# mainAD2S1200.net
KiCad netlist of a schematic drawn in EAGLE
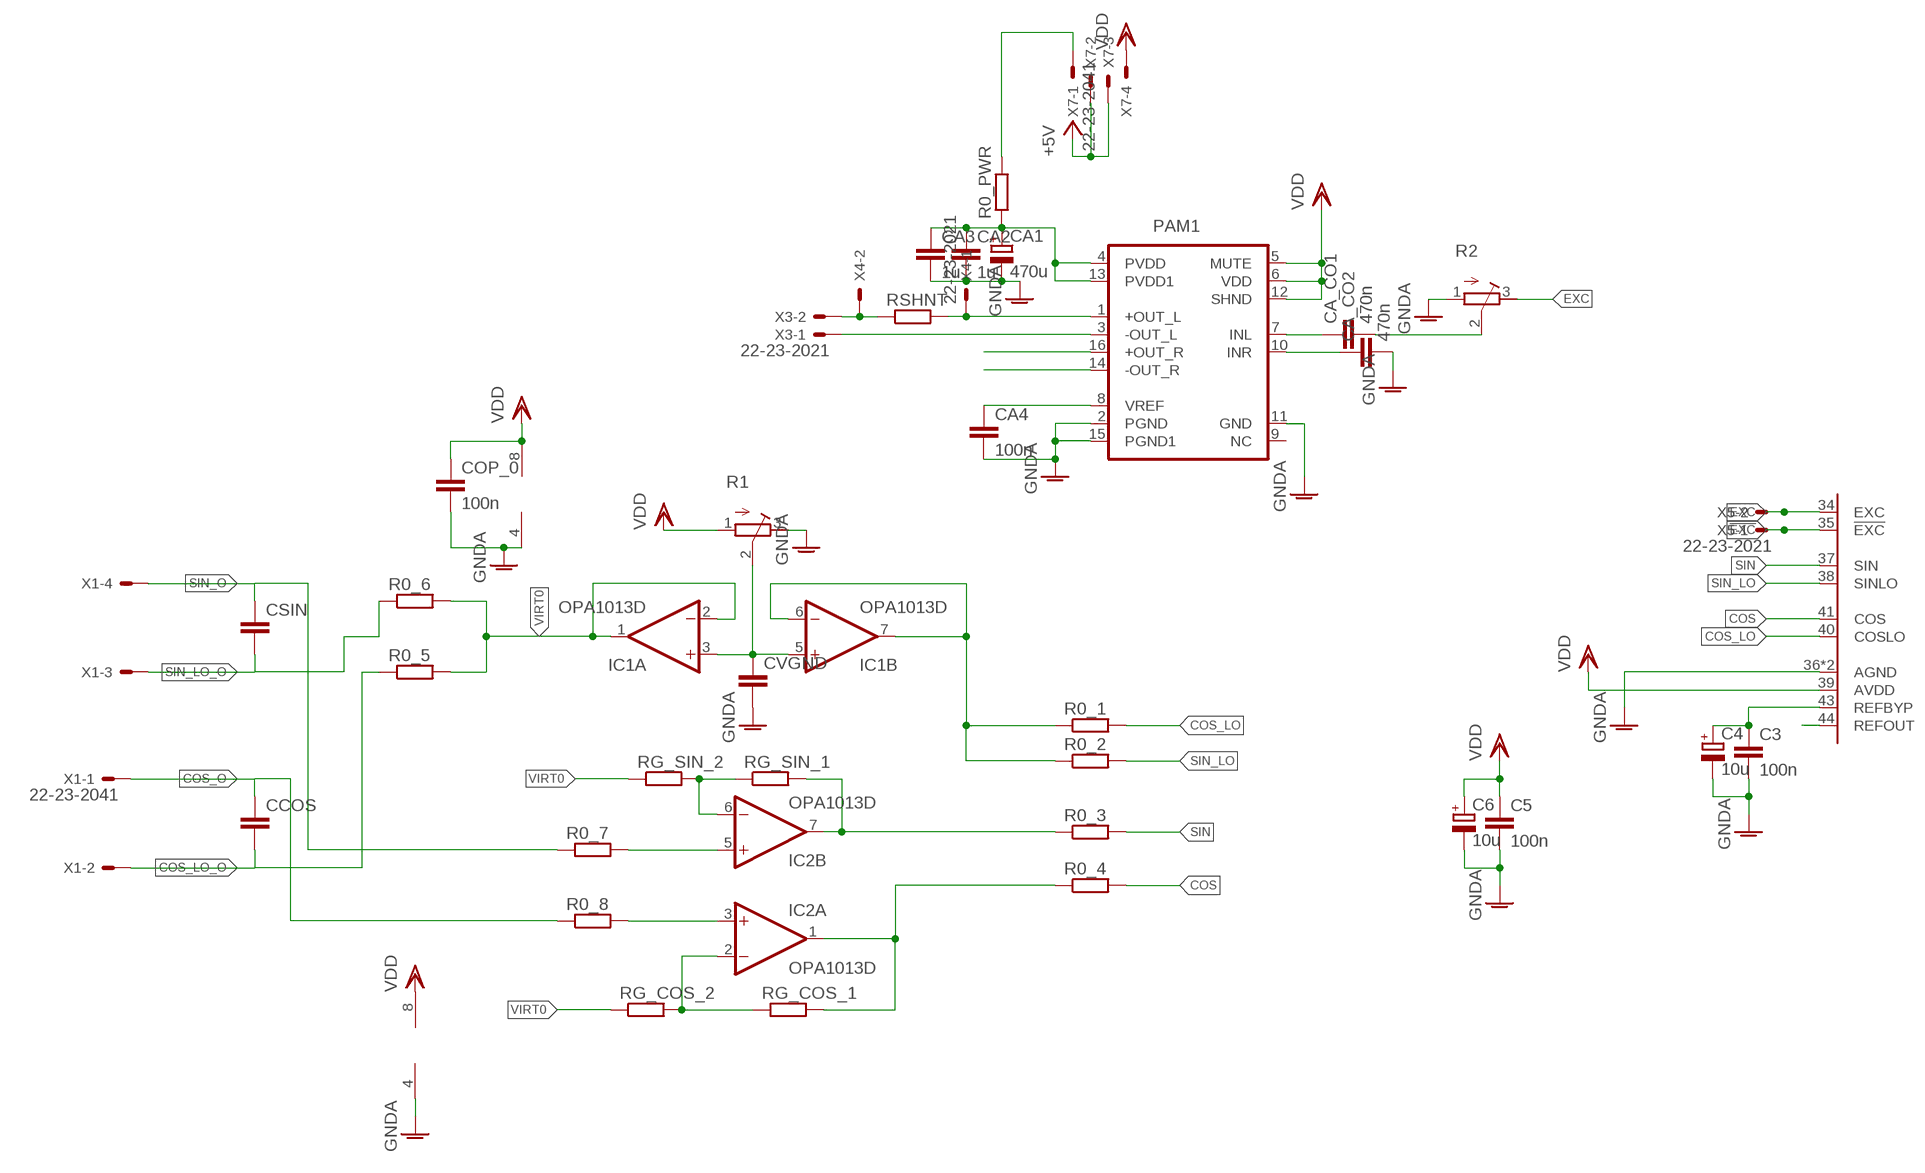
[diagram p0: schematic, sheet 1, part 1 of 2]
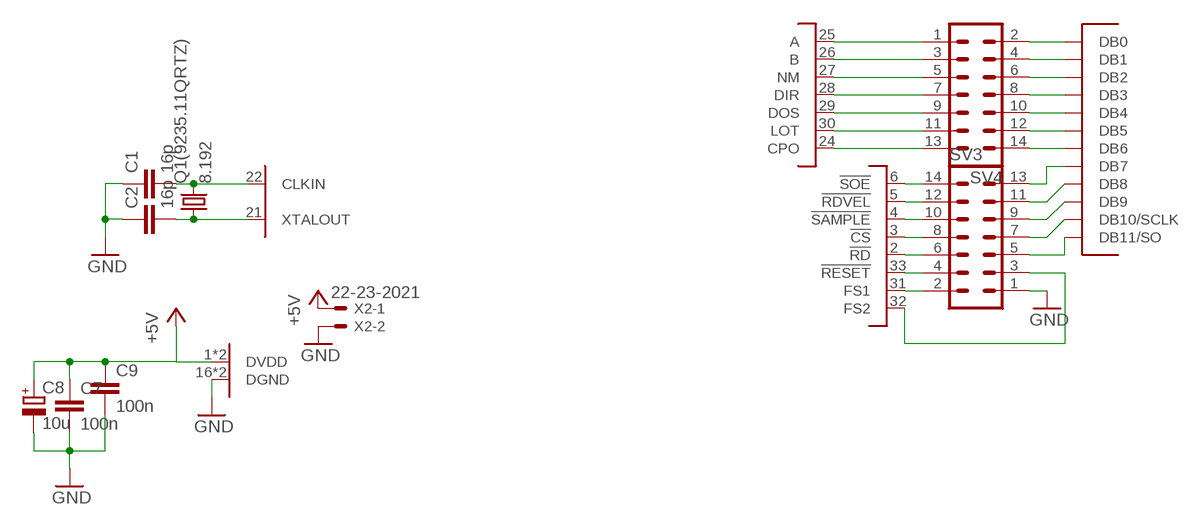
[diagram p1: schematic, sheet 1, part 2 of 2]

(export (version "E")
  (design (tool "Eeschema 10.0.6"))
  (components
    (comp (ref "C1")
      (value "16p")
      (footprint "eagle-import:C0805")
      (libsource (lib "eagle-import") (part "C-EUC0805"))
    )
    (comp (ref "C2")
      (value "16p")
      (footprint "eagle-import:C0805")
      (libsource (lib "eagle-import") (part "C-EUC0805"))
    )
    (comp (ref "C3")
      (value "100n")
      (footprint "eagle-import:C0805")
      (libsource (lib "eagle-import") (part "C-EUC0805"))
    )
    (comp (ref "C4")
      (value "10u")
      (footprint "eagle-import:SMC_A")
      (libsource (lib "eagle-import") (part "CPOL-EUSMCA"))
    )
    (comp (ref "C5")
      (value "100n")
      (footprint "eagle-import:C0805")
      (libsource (lib "eagle-import") (part "C-EUC0805"))
    )
    (comp (ref "C6")
      (value "10u")
      (footprint "eagle-import:SMC_A")
      (libsource (lib "eagle-import") (part "CPOL-EUSMCA"))
    )
    (comp (ref "C7")
      (value "100n")
      (footprint "eagle-import:C0805")
      (libsource (lib "eagle-import") (part "C-EUC0805"))
    )
    (comp (ref "C8")
      (value "10u")
      (footprint "eagle-import:SMC_A")
      (libsource (lib "eagle-import") (part "CPOL-EUSMCA"))
    )
    (comp (ref "C9")
      (value "100n")
      (footprint "eagle-import:C0805")
      (libsource (lib "eagle-import") (part "C-EUC0805"))
    )
    (comp (ref "CA1")
      (value "470u")
      (footprint "eagle-import:EB25D")
      (libsource (lib "eagle-import") (part "CPOL-EUE10-25"))
    )
    (comp (ref "CA2")
      (value "1u")
      (footprint "eagle-import:C1206")
      (libsource (lib "eagle-import") (part "resistor_C-EUC1206"))
    )
    (comp (ref "CA3")
      (value "1u")
      (footprint "eagle-import:C1206")
      (libsource (lib "eagle-import") (part "resistor_C-EUC1206"))
    )
    (comp (ref "CA4")
      (value "100n")
      (footprint "eagle-import:C0805")
      (libsource (lib "eagle-import") (part "C-EUC0805"))
    )
    (comp (ref "CA_CO1")
      (value "470n")
      (footprint "eagle-import:C0805")
      (libsource (lib "eagle-import") (part "resistor_C-EUC0805"))
    )
    (comp (ref "CA_CO2")
      (value "470n")
      (footprint "eagle-import:C0805")
      (libsource (lib "eagle-import") (part "resistor_C-EUC0805"))
    )
    (comp (ref "CCOS")
      (value "C-EUC0805")
      (footprint "eagle-import:C0805")
      (libsource (lib "eagle-import") (part "C-EUC0805"))
    )
    (comp (ref "COP_0")
      (value "100n")
      (footprint "eagle-import:C0805")
      (libsource (lib "eagle-import") (part "C-EUC0805"))
    )
    (comp (ref "CSIN")
      (value "C-EUC0805")
      (footprint "eagle-import:C0805")
      (libsource (lib "eagle-import") (part "C-EUC0805"))
    )
    (comp (ref "CVGND")
      (value "C-EUC0805")
      (footprint "eagle-import:C0805")
      (libsource (lib "eagle-import") (part "C-EUC0805"))
    )
    (comp (ref "IC1")
      (value "OPA1013D")
      (footprint "eagle-import:SO08")
      (libsource (lib "eagle-import") (part "OPA1013D"))
    )
    (comp (ref "IC2")
      (value "OPA1013D")
      (footprint "eagle-import:SO08")
      (libsource (lib "eagle-import") (part "OPA1013D"))
    )
    (comp (ref "PAM1")
      (value "PAM8403")
      (footprint "eagle-import:SOP-16")
      (libsource (lib "eagle-import") (part "PAM8403"))
    )
    (comp (ref "Q1(9235.11QRTZ)")
      (value "8.192")
      (footprint "eagle-import:CTS406")
      (libsource (lib "eagle-import") (part "CRYSTALCTS406"))
    )
    (comp (ref "R0_1")
      (value "R-EU_R0805")
      (footprint "eagle-import:R0805")
      (libsource (lib "eagle-import") (part "R-EU_R0805"))
    )
    (comp (ref "R0_2")
      (value "R-EU_R0805")
      (footprint "eagle-import:R0805")
      (libsource (lib "eagle-import") (part "R-EU_R0805"))
    )
    (comp (ref "R0_3")
      (value "R-EU_R0805")
      (footprint "eagle-import:R0805")
      (libsource (lib "eagle-import") (part "R-EU_R0805"))
    )
    (comp (ref "R0_4")
      (value "R-EU_R0805")
      (footprint "eagle-import:R0805")
      (libsource (lib "eagle-import") (part "R-EU_R0805"))
    )
    (comp (ref "R0_5")
      (value "R-EU_R0805")
      (footprint "eagle-import:R0805")
      (libsource (lib "eagle-import") (part "R-EU_R0805"))
    )
    (comp (ref "R0_6")
      (value "R-EU_R0805")
      (footprint "eagle-import:R0805")
      (libsource (lib "eagle-import") (part "R-EU_R0805"))
    )
    (comp (ref "R0_7")
      (value "R-EU_R0805")
      (footprint "eagle-import:R0805")
      (libsource (lib "eagle-import") (part "R-EU_R0805"))
    )
    (comp (ref "R0_8")
      (value "R-EU_R0805")
      (footprint "eagle-import:R0805")
      (libsource (lib "eagle-import") (part "R-EU_R0805"))
    )
    (comp (ref "R0_PWR")
      (value "R-EU_R0805")
      (footprint "eagle-import:R0805")
      (libsource (lib "eagle-import") (part "R-EU_R0805"))
    )
    (comp (ref "R1")
      (value "R-TRIMM64X")
      (footprint "eagle-import:RTRIM64X")
      (libsource (lib "eagle-import") (part "R-TRIMM64X"))
    )
    (comp (ref "R2")
      (value "R-TRIMM64X")
      (footprint "eagle-import:RTRIM64X")
      (libsource (lib "eagle-import") (part "R-TRIMM64X"))
    )
    (comp (ref "RG_COS_1")
      (value "R-EU_R0805")
      (footprint "eagle-import:R0805")
      (libsource (lib "eagle-import") (part "R-EU_R0805"))
    )
    (comp (ref "RG_COS_2")
      (value "R-EU_R0805")
      (footprint "eagle-import:R0805")
      (libsource (lib "eagle-import") (part "R-EU_R0805"))
    )
    (comp (ref "RG_SIN_1")
      (value "R-EU_R0805")
      (footprint "eagle-import:R0805")
      (libsource (lib "eagle-import") (part "R-EU_R0805"))
    )
    (comp (ref "RG_SIN_2")
      (value "R-EU_R0805")
      (footprint "eagle-import:R0805")
      (libsource (lib "eagle-import") (part "R-EU_R0805"))
    )
    (comp (ref "RSHNT")
      (value "R-EU_R0805")
      (footprint "eagle-import:R0805")
      (libsource (lib "eagle-import") (part "R-EU_R0805"))
    )
    (comp (ref "SV3")
      (value "ML14")
      (footprint "eagle-import:ML14")
      (libsource (lib "eagle-import") (part "ML14"))
    )
    (comp (ref "SV4")
      (value "ML14")
      (footprint "eagle-import:ML14")
      (libsource (lib "eagle-import") (part "ML14"))
    )
    (comp (ref "U$1")
      (value "AD1S1200")
      (footprint "eagle-import:TQFP-44")
      (libsource (lib "eagle-import") (part "AD1S1200"))
    )
    (comp (ref "X1")
      (value "22-23-2041")
      (footprint "eagle-import:22-23-2041")
      (fields (field (name "MF") "MOLEX"))
      (libsource (lib "eagle-import") (part "22-23-2041"))
    )
    (comp (ref "X2")
      (value "22-23-2021")
      (footprint "eagle-import:22-23-2021")
      (fields (field (name "MF") "MOLEX"))
      (libsource (lib "eagle-import") (part "22-23-2021"))
    )
    (comp (ref "X3")
      (value "22-23-2021")
      (footprint "eagle-import:22-23-2021")
      (fields (field (name "MF") "MOLEX"))
      (libsource (lib "eagle-import") (part "22-23-2021"))
    )
    (comp (ref "X4")
      (value "22-23-2021")
      (footprint "eagle-import:22-23-2021")
      (fields (field (name "MF") "MOLEX"))
      (libsource (lib "eagle-import") (part "22-23-2021"))
    )
    (comp (ref "X5")
      (value "22-23-2021")
      (footprint "eagle-import:22-23-2021")
      (fields (field (name "MF") "MOLEX"))
      (libsource (lib "eagle-import") (part "22-23-2021"))
    )
    (comp (ref "X7")
      (value "22-23-2041")
      (footprint "eagle-import:22-23-2041")
      (fields (field (name "MF") "MOLEX"))
      (libsource (lib "eagle-import") (part "22-23-2041"))
    )
  )
  (nets
    (net (code "1") (name "+5V") (class "Default")
      (node (ref "C7") (pin "1") (pinfunction "1_1") (pintype "passive"))
      (node (ref "C8") (pin "+") (pinfunction "+_+") (pintype "passive"))
      (node (ref "C9") (pin "1") (pinfunction "1_1") (pintype "passive"))
      (node (ref "U$1") (pin "1") (pinfunction "DVDD_1") (pintype "bidirectional"))
      (node (ref "U$1") (pin "17") (pinfunction "DVDD_17") (pintype "bidirectional"))
      (node (ref "X2") (pin "1") (pinfunction "S_1") (pintype "passive"))
      (node (ref "X7") (pin "2") (pinfunction "S_2") (pintype "passive"))
      (node (ref "X7") (pin "3") (pinfunction "S_3") (pintype "passive"))
    )
    (net (code "2") (name "/~{EXC}") (class "Default")
      (node (ref "U$1") (pin "35") (pinfunction "~{EXC}_35") (pintype "bidirectional"))
      (node (ref "X5") (pin "1") (pinfunction "S_1") (pintype "passive"))
    )
    (net (code "3") (name "COS") (class "Default")
      (node (ref "R0_4") (pin "2") (pinfunction "2_2") (pintype "passive"))
      (node (ref "U$1") (pin "41") (pinfunction "COS_41") (pintype "bidirectional"))
    )
    (net (code "4") (name "COS_LO") (class "Default")
      (node (ref "R0_1") (pin "2") (pinfunction "2_2") (pintype "passive"))
      (node (ref "U$1") (pin "40") (pinfunction "COSLO_40") (pintype "bidirectional"))
    )
    (net (code "5") (name "COS_LO_O") (class "Default")
      (node (ref "CCOS") (pin "2") (pinfunction "2_2") (pintype "passive"))
      (node (ref "R0_5") (pin "1") (pinfunction "1_1") (pintype "passive"))
      (node (ref "X1") (pin "2") (pinfunction "S_2") (pintype "passive"))
    )
    (net (code "6") (name "COS_O") (class "Default")
      (node (ref "CCOS") (pin "1") (pinfunction "1_1") (pintype "passive"))
      (node (ref "R0_8") (pin "1") (pinfunction "1_1") (pintype "passive"))
      (node (ref "X1") (pin "1") (pinfunction "S_1") (pintype "passive"))
    )
    (net (code "7") (name "EXC") (class "Default")
      (node (ref "R2") (pin "3") (pinfunction "E_3") (pintype "passive"))
      (node (ref "U$1") (pin "34") (pinfunction "EXC_34") (pintype "bidirectional"))
      (node (ref "X5") (pin "2") (pinfunction "S_2") (pintype "passive"))
    )
    (net (code "8") (name "GND") (class "Default")
      (node (ref "C1") (pin "1") (pinfunction "1_1") (pintype "passive"))
      (node (ref "C2") (pin "1") (pinfunction "1_1") (pintype "passive"))
      (node (ref "C7") (pin "2") (pinfunction "2_2") (pintype "passive"))
      (node (ref "C8") (pin "-") (pinfunction "-_-") (pintype "passive"))
      (node (ref "C9") (pin "2") (pinfunction "2_2") (pintype "passive"))
      (node (ref "SV3") (pin "1") (pinfunction "1_1") (pintype "passive"))
      (node (ref "U$1") (pin "16") (pinfunction "DGND_16") (pintype "bidirectional"))
      (node (ref "U$1") (pin "23") (pinfunction "DGND_23") (pintype "bidirectional"))
      (node (ref "X2") (pin "2") (pinfunction "S_2") (pintype "passive"))
    )
    (net (code "9") (name "GNDA") (class "Default")
      (node (ref "C3") (pin "2") (pinfunction "2_2") (pintype "passive"))
      (node (ref "C4") (pin "-") (pinfunction "-_-") (pintype "passive"))
      (node (ref "C5") (pin "2") (pinfunction "2_2") (pintype "passive"))
      (node (ref "C6") (pin "-") (pinfunction "-_-") (pintype "passive"))
      (node (ref "CA1") (pin "-") (pinfunction "-_-") (pintype "passive"))
      (node (ref "CA2") (pin "2") (pinfunction "2_2") (pintype "passive"))
      (node (ref "CA3") (pin "2") (pinfunction "2_2") (pintype "passive"))
      (node (ref "CA4") (pin "2") (pinfunction "2_2") (pintype "passive"))
      (node (ref "CA_CO2") (pin "2") (pinfunction "2_2") (pintype "passive"))
      (node (ref "COP_0") (pin "2") (pinfunction "2_2") (pintype "passive"))
      (node (ref "CVGND") (pin "2") (pinfunction "2_2") (pintype "passive"))
      (node (ref "IC1") (pin "4") (pinfunction "V-_4") (pintype "power_in"))
      (node (ref "IC2") (pin "4") (pinfunction "V-_4") (pintype "power_in"))
      (node (ref "PAM1") (pin "11") (pinfunction "GND_11") (pintype "output"))
      (node (ref "PAM1") (pin "15") (pinfunction "PGND1_15") (pintype "output"))
      (node (ref "PAM1") (pin "2") (pinfunction "PGND_2") (pintype "input"))
      (node (ref "R1") (pin "3") (pinfunction "E_3") (pintype "passive"))
      (node (ref "R2") (pin "1") (pinfunction "A_1") (pintype "passive"))
      (node (ref "U$1") (pin "36") (pinfunction "AGND_36") (pintype "bidirectional"))
      (node (ref "U$1") (pin "42") (pinfunction "AGND_42") (pintype "bidirectional"))
    )
    (net (code "10") (name "Net-(IC1A-+IN)") (class "Default")
      (node (ref "CVGND") (pin "1") (pinfunction "1_1") (pintype "passive"))
      (node (ref "IC1") (pin "3") (pinfunction "+IN_3") (pintype "input"))
      (node (ref "IC1") (pin "5") (pinfunction "+IN_5") (pintype "input"))
      (node (ref "R1") (pin "2") (pinfunction "S_2") (pintype "passive"))
    )
    (net (code "11") (name "Net-(IC1B--IN)") (class "Default")
      (node (ref "IC1") (pin "6") (pinfunction "-IN_6") (pintype "input"))
      (node (ref "IC1") (pin "7") (pinfunction "OUT_7") (pintype "output"))
      (node (ref "R0_1") (pin "1") (pinfunction "1_1") (pintype "passive"))
      (node (ref "R0_2") (pin "1") (pinfunction "1_1") (pintype "passive"))
    )
    (net (code "12") (name "Net-(IC2A-+IN)") (class "Default")
      (node (ref "IC2") (pin "3") (pinfunction "+IN_3") (pintype "input"))
      (node (ref "R0_8") (pin "2") (pinfunction "2_2") (pintype "passive"))
    )
    (net (code "13") (name "Net-(IC2A--IN)") (class "Default")
      (node (ref "IC2") (pin "2") (pinfunction "-IN_2") (pintype "input"))
      (node (ref "RG_COS_1") (pin "1") (pinfunction "1_1") (pintype "passive"))
      (node (ref "RG_COS_2") (pin "2") (pinfunction "2_2") (pintype "passive"))
    )
    (net (code "14") (name "Net-(IC2A-OUT)") (class "Default")
      (node (ref "IC2") (pin "1") (pinfunction "OUT_1") (pintype "output"))
      (node (ref "R0_4") (pin "1") (pinfunction "1_1") (pintype "passive"))
      (node (ref "RG_COS_1") (pin "2") (pinfunction "2_2") (pintype "passive"))
    )
    (net (code "15") (name "Net-(IC2B-+IN)") (class "Default")
      (node (ref "IC2") (pin "5") (pinfunction "+IN_5") (pintype "input"))
      (node (ref "R0_7") (pin "2") (pinfunction "2_2") (pintype "passive"))
    )
    (net (code "16") (name "Net-(IC2B--IN)") (class "Default")
      (node (ref "IC2") (pin "6") (pinfunction "-IN_6") (pintype "input"))
      (node (ref "RG_SIN_1") (pin "1") (pinfunction "1_1") (pintype "passive"))
      (node (ref "RG_SIN_2") (pin "2") (pinfunction "2_2") (pintype "passive"))
    )
    (net (code "17") (name "Net-(IC2B-OUT)") (class "Default")
      (node (ref "IC2") (pin "7") (pinfunction "OUT_7") (pintype "output"))
      (node (ref "R0_3") (pin "1") (pinfunction "1_1") (pintype "passive"))
      (node (ref "RG_SIN_1") (pin "2") (pinfunction "2_2") (pintype "passive"))
    )
    (net (code "18") (name "Net-(PAM1-+OUT_L)") (class "Default")
      (node (ref "PAM1") (pin "1") (pinfunction "+OUT_L_1") (pintype "input"))
      (node (ref "RSHNT") (pin "2") (pinfunction "2_2") (pintype "passive"))
      (node (ref "X4") (pin "1") (pinfunction "S_1") (pintype "passive"))
    )
    (net (code "19") (name "Net-(PAM1--OUT_L)") (class "Default")
      (node (ref "PAM1") (pin "3") (pinfunction "-OUT_L_3") (pintype "input"))
      (node (ref "X3") (pin "1") (pinfunction "S_1") (pintype "passive"))
    )
    (net (code "20") (name "Net-(PAM1-INL)") (class "Default")
      (node (ref "CA_CO1") (pin "1") (pinfunction "1_1") (pintype "passive"))
      (node (ref "PAM1") (pin "7") (pinfunction "INL_7") (pintype "input"))
    )
    (net (code "21") (name "Net-(PAM1-INR)") (class "Default")
      (node (ref "CA_CO2") (pin "1") (pinfunction "1_1") (pintype "passive"))
      (node (ref "PAM1") (pin "10") (pinfunction "INR_10") (pintype "output"))
    )
    (net (code "22") (name "Net-(PAM1-PVDD)") (class "Default")
      (node (ref "CA1") (pin "+") (pinfunction "+_+") (pintype "passive"))
      (node (ref "CA2") (pin "1") (pinfunction "1_1") (pintype "passive"))
      (node (ref "CA3") (pin "1") (pinfunction "1_1") (pintype "passive"))
      (node (ref "PAM1") (pin "13") (pinfunction "PVDD1_13") (pintype "output"))
      (node (ref "PAM1") (pin "4") (pinfunction "PVDD_4") (pintype "input"))
      (node (ref "R0_PWR") (pin "1") (pinfunction "1_1") (pintype "passive"))
    )
    (net (code "23") (name "Net-(PAM1-VREF)") (class "Default")
      (node (ref "CA4") (pin "1") (pinfunction "1_1") (pintype "passive"))
      (node (ref "PAM1") (pin "8") (pinfunction "VREF_8") (pintype "input"))
    )
    (net (code "24") (name "Net-(Q1(9235.11QRTZ)-2)") (class "Default")
      (node (ref "C1") (pin "2") (pinfunction "2_2") (pintype "passive"))
      (node (ref "Q1(9235.11QRTZ)") (pin "3") (pinfunction "2_3") (pintype "passive"))
      (node (ref "U$1") (pin "22") (pinfunction "CLKIN_22") (pintype "bidirectional"))
    )
    (net (code "25") (name "Net-(R2-S)") (class "Default")
      (node (ref "CA_CO1") (pin "2") (pinfunction "2_2") (pintype "passive"))
      (node (ref "R2") (pin "2") (pinfunction "S_2") (pintype "passive"))
    )
    (net (code "26") (name "Net-(U$1A-XTALOUT)") (class "Default")
      (node (ref "C2") (pin "2") (pinfunction "2_2") (pintype "passive"))
      (node (ref "Q1(9235.11QRTZ)") (pin "1") (pinfunction "1_1") (pintype "passive"))
      (node (ref "U$1") (pin "21") (pinfunction "XTALOUT_21") (pintype "bidirectional"))
    )
    (net (code "27") (name "Net-(U$1B-FS1)") (class "Default")
      (node (ref "SV3") (pin "2") (pinfunction "2_2") (pintype "passive"))
      (node (ref "U$1") (pin "31") (pinfunction "FS1_31") (pintype "bidirectional"))
    )
    (net (code "28") (name "Net-(U$1B-FS2)") (class "Default")
      (node (ref "SV3") (pin "3") (pinfunction "3_3") (pintype "passive"))
      (node (ref "U$1") (pin "32") (pinfunction "FS2_32") (pintype "bidirectional"))
    )
    (net (code "29") (name "Net-(U$1B-~{CS})") (class "Default")
      (node (ref "SV3") (pin "8") (pinfunction "8_8") (pintype "passive"))
      (node (ref "U$1") (pin "3") (pinfunction "~{CS}_3") (pintype "bidirectional"))
    )
    (net (code "30") (name "Net-(U$1B-~{RDVEL})") (class "Default")
      (node (ref "SV3") (pin "12") (pinfunction "12_12") (pintype "passive"))
      (node (ref "U$1") (pin "5") (pinfunction "~{RDVEL}_5") (pintype "bidirectional"))
    )
    (net (code "31") (name "Net-(U$1B-~{RD})") (class "Default")
      (node (ref "SV3") (pin "6") (pinfunction "6_6") (pintype "passive"))
      (node (ref "U$1") (pin "2") (pinfunction "~{RD}_2") (pintype "bidirectional"))
    )
    (net (code "32") (name "Net-(U$1B-~{RESET})") (class "Default")
      (node (ref "SV3") (pin "4") (pinfunction "4_4") (pintype "passive"))
      (node (ref "U$1") (pin "33") (pinfunction "~{RESET}_33") (pintype "bidirectional"))
    )
    (net (code "33") (name "Net-(U$1B-~{SAMPLE})") (class "Default")
      (node (ref "SV3") (pin "10") (pinfunction "10_10") (pintype "passive"))
      (node (ref "U$1") (pin "4") (pinfunction "~{SAMPLE}_4") (pintype "bidirectional"))
    )
    (net (code "34") (name "Net-(U$1B-~{SOE})") (class "Default")
      (node (ref "SV3") (pin "14") (pinfunction "14_14") (pintype "passive"))
      (node (ref "U$1") (pin "6") (pinfunction "~{SOE}_6") (pintype "bidirectional"))
    )
    (net (code "35") (name "Net-(U$1C-A)") (class "Default")
      (node (ref "SV4") (pin "1") (pinfunction "1_1") (pintype "passive"))
      (node (ref "U$1") (pin "25") (pinfunction "A_25") (pintype "bidirectional"))
    )
    (net (code "36") (name "Net-(U$1C-B)") (class "Default")
      (node (ref "SV4") (pin "3") (pinfunction "3_3") (pintype "passive"))
      (node (ref "U$1") (pin "26") (pinfunction "B_26") (pintype "bidirectional"))
    )
    (net (code "37") (name "Net-(U$1C-CPO)") (class "Default")
      (node (ref "SV4") (pin "13") (pinfunction "13_13") (pintype "passive"))
      (node (ref "U$1") (pin "24") (pinfunction "CPO_24") (pintype "bidirectional"))
    )
    (net (code "38") (name "Net-(U$1C-DIR)") (class "Default")
      (node (ref "SV4") (pin "7") (pinfunction "7_7") (pintype "passive"))
      (node (ref "U$1") (pin "28") (pinfunction "DIR_28") (pintype "bidirectional"))
    )
    (net (code "39") (name "Net-(U$1C-DOS)") (class "Default")
      (node (ref "SV4") (pin "9") (pinfunction "9_9") (pintype "passive"))
      (node (ref "U$1") (pin "29") (pinfunction "DOS_29") (pintype "bidirectional"))
    )
    (net (code "40") (name "Net-(U$1C-LOT)") (class "Default")
      (node (ref "SV4") (pin "11") (pinfunction "11_11") (pintype "passive"))
      (node (ref "U$1") (pin "30") (pinfunction "LOT_30") (pintype "bidirectional"))
    )
    (net (code "41") (name "Net-(U$1C-NM)") (class "Default")
      (node (ref "SV4") (pin "5") (pinfunction "5_5") (pintype "passive"))
      (node (ref "U$1") (pin "27") (pinfunction "NM_27") (pintype "bidirectional"))
    )
    (net (code "42") (name "Net-(U$1D-DB0)") (class "Default")
      (node (ref "SV4") (pin "2") (pinfunction "2_2") (pintype "passive"))
      (node (ref "U$1") (pin "20") (pinfunction "DB0_20") (pintype "bidirectional"))
    )
    (net (code "43") (name "Net-(U$1D-DB1)") (class "Default")
      (node (ref "SV4") (pin "4") (pinfunction "4_4") (pintype "passive"))
      (node (ref "U$1") (pin "19") (pinfunction "DB1_19") (pintype "bidirectional"))
    )
    (net (code "44") (name "Net-(U$1D-DB2)") (class "Default")
      (node (ref "SV4") (pin "6") (pinfunction "6_6") (pintype "passive"))
      (node (ref "U$1") (pin "18") (pinfunction "DB2_18") (pintype "bidirectional"))
    )
    (net (code "45") (name "Net-(U$1D-DB3)") (class "Default")
      (node (ref "SV4") (pin "8") (pinfunction "8_8") (pintype "passive"))
      (node (ref "U$1") (pin "15") (pinfunction "DB3_15") (pintype "bidirectional"))
    )
    (net (code "46") (name "Net-(U$1D-DB4)") (class "Default")
      (node (ref "SV4") (pin "10") (pinfunction "10_10") (pintype "passive"))
      (node (ref "U$1") (pin "14") (pinfunction "DB4_14") (pintype "bidirectional"))
    )
    (net (code "47") (name "Net-(U$1D-DB5)") (class "Default")
      (node (ref "SV4") (pin "12") (pinfunction "12_12") (pintype "passive"))
      (node (ref "U$1") (pin "13") (pinfunction "DB5_13") (pintype "bidirectional"))
    )
    (net (code "48") (name "Net-(U$1D-DB6)") (class "Default")
      (node (ref "SV4") (pin "14") (pinfunction "14_14") (pintype "passive"))
      (node (ref "U$1") (pin "12") (pinfunction "DB6_12") (pintype "bidirectional"))
    )
    (net (code "49") (name "Net-(U$1D-DB7)") (class "Default")
      (node (ref "SV3") (pin "13") (pinfunction "13_13") (pintype "passive"))
      (node (ref "U$1") (pin "11") (pinfunction "DB7_11") (pintype "bidirectional"))
    )
    (net (code "50") (name "Net-(U$1D-DB8)") (class "Default")
      (node (ref "SV3") (pin "11") (pinfunction "11_11") (pintype "passive"))
      (node (ref "U$1") (pin "10") (pinfunction "DB8_10") (pintype "bidirectional"))
    )
    (net (code "51") (name "Net-(U$1D-DB9)") (class "Default")
      (node (ref "SV3") (pin "9") (pinfunction "9_9") (pintype "passive"))
      (node (ref "U$1") (pin "9") (pinfunction "DB9_9") (pintype "bidirectional"))
    )
    (net (code "52") (name "Net-(U$1D-DB10{slash}SCLK)") (class "Default")
      (node (ref "SV3") (pin "7") (pinfunction "7_7") (pintype "passive"))
      (node (ref "U$1") (pin "8") (pinfunction "DB10/SCLK_8") (pintype "bidirectional"))
    )
    (net (code "53") (name "Net-(U$1D-DB11{slash}SO)") (class "Default")
      (node (ref "SV3") (pin "5") (pinfunction "5_5") (pintype "passive"))
      (node (ref "U$1") (pin "7") (pinfunction "DB11/SO_7") (pintype "bidirectional"))
    )
    (net (code "54") (name "Net-(U$1E-REFBYP)") (class "Default")
      (node (ref "C3") (pin "1") (pinfunction "1_1") (pintype "passive"))
      (node (ref "C4") (pin "+") (pinfunction "+_+") (pintype "passive"))
      (node (ref "U$1") (pin "43") (pinfunction "REFBYP_43") (pintype "bidirectional"))
    )
    (net (code "55") (name "Net-(X3B-S)") (class "Default")
      (node (ref "RSHNT") (pin "1") (pinfunction "1_1") (pintype "passive"))
      (node (ref "X3") (pin "2") (pinfunction "S_2") (pintype "passive"))
      (node (ref "X4") (pin "2") (pinfunction "S_2") (pintype "passive"))
    )
    (net (code "56") (name "Net-(X7A-S)") (class "Default")
      (node (ref "R0_PWR") (pin "2") (pinfunction "2_2") (pintype "passive"))
      (node (ref "X7") (pin "1") (pinfunction "S_1") (pintype "passive"))
    )
    (net (code "57") (name "SIN") (class "Default")
      (node (ref "R0_3") (pin "2") (pinfunction "2_2") (pintype "passive"))
      (node (ref "U$1") (pin "37") (pinfunction "SIN_37") (pintype "bidirectional"))
    )
    (net (code "58") (name "SIN_LO") (class "Default")
      (node (ref "R0_2") (pin "2") (pinfunction "2_2") (pintype "passive"))
      (node (ref "U$1") (pin "38") (pinfunction "SINLO_38") (pintype "bidirectional"))
    )
    (net (code "59") (name "SIN_LO_O") (class "Default")
      (node (ref "CSIN") (pin "2") (pinfunction "2_2") (pintype "passive"))
      (node (ref "R0_6") (pin "1") (pinfunction "1_1") (pintype "passive"))
      (node (ref "X1") (pin "3") (pinfunction "S_3") (pintype "passive"))
    )
    (net (code "60") (name "SIN_O") (class "Default")
      (node (ref "CSIN") (pin "1") (pinfunction "1_1") (pintype "passive"))
      (node (ref "R0_7") (pin "1") (pinfunction "1_1") (pintype "passive"))
      (node (ref "X1") (pin "4") (pinfunction "S_4") (pintype "passive"))
    )
    (net (code "61") (name "VDD") (class "Default")
      (node (ref "C5") (pin "1") (pinfunction "1_1") (pintype "passive"))
      (node (ref "C6") (pin "+") (pinfunction "+_+") (pintype "passive"))
      (node (ref "COP_0") (pin "1") (pinfunction "1_1") (pintype "passive"))
      (node (ref "IC1") (pin "8") (pinfunction "V+_8") (pintype "power_in"))
      (node (ref "IC2") (pin "8") (pinfunction "V+_8") (pintype "power_in"))
      (node (ref "PAM1") (pin "12") (pinfunction "SHND_12") (pintype "output"))
      (node (ref "PAM1") (pin "5") (pinfunction "MUTE_5") (pintype "input"))
      (node (ref "PAM1") (pin "6") (pinfunction "VDD_6") (pintype "input"))
      (node (ref "R1") (pin "1") (pinfunction "A_1") (pintype "passive"))
      (node (ref "U$1") (pin "39") (pinfunction "AVDD_39") (pintype "bidirectional"))
      (node (ref "X7") (pin "4") (pinfunction "S_4") (pintype "passive"))
    )
    (net (code "62") (name "VIRT0") (class "Default")
      (node (ref "IC1") (pin "1") (pinfunction "OUT_1") (pintype "output"))
      (node (ref "IC1") (pin "2") (pinfunction "-IN_2") (pintype "input"))
      (node (ref "R0_5") (pin "2") (pinfunction "2_2") (pintype "passive"))
      (node (ref "R0_6") (pin "2") (pinfunction "2_2") (pintype "passive"))
      (node (ref "RG_COS_2") (pin "1") (pinfunction "1_1") (pintype "passive"))
      (node (ref "RG_SIN_2") (pin "1") (pinfunction "1_1") (pintype "passive"))
    )
    (net (code "63") (name "unconnected-(PAM1-+OUT_R-Pad16)") (class "Default")
      (node (ref "PAM1") (pin "16") (pinfunction "+OUT_R_16") (pintype "output"))
    )
    (net (code "64") (name "unconnected-(PAM1--OUT_R-Pad14)") (class "Default")
      (node (ref "PAM1") (pin "14") (pinfunction "-OUT_R_14") (pintype "output"))
    )
    (net (code "65") (name "unconnected-(PAM1-NC-Pad9)") (class "Default")
      (node (ref "PAM1") (pin "9") (pinfunction "NC_9") (pintype "output"))
    )
    (net (code "66") (name "unconnected-(U$1E-REFOUT-Pad44)") (class "Default")
      (node (ref "U$1") (pin "44") (pinfunction "REFOUT_44") (pintype "bidirectional"))
    )
  )
)
